# Sheet7.net
KiCad netlist of a schematic drawn in Altium Designer
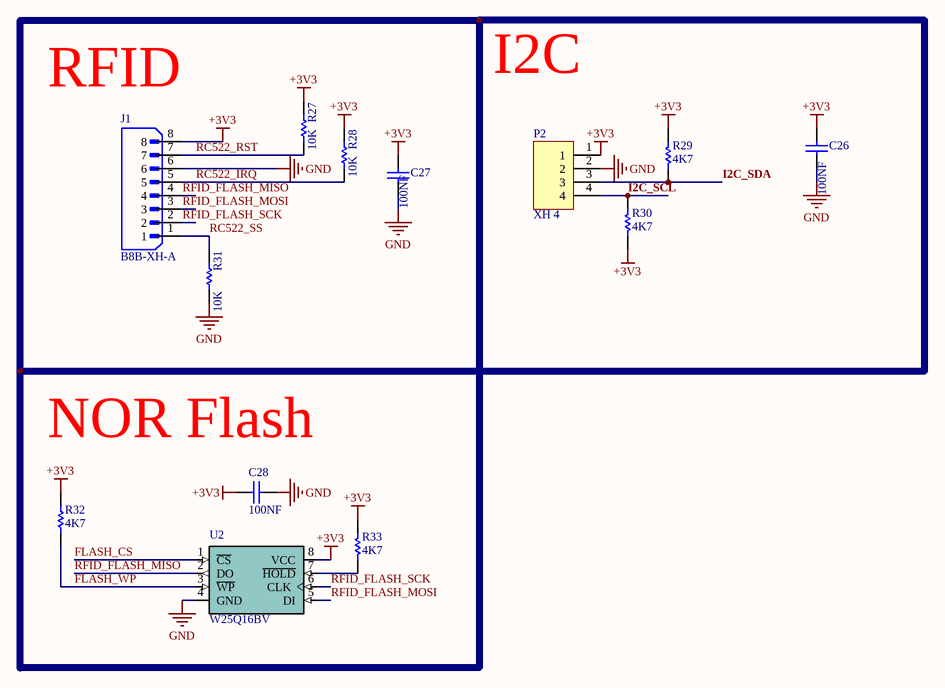
[diagram p0: Sheet7.SchDoc]

(export (version "E")
  (design (tool "Eeschema 10.0.6"))
  (components
    (comp (ref "C26")
      (value "100NF")
      (footprint "CAP0603")
      (description "TOTAL CAPACITOR SMD PACK")
      (fields (field (name "DESIGNER") "Abbas Basereh"))
      (libsource (lib "Altium") (part "CAP SMD PACKAGE"))
    )
    (comp (ref "C27")
      (value "100NF")
      (footprint "CAP0603")
      (description "TOTAL CAPACITOR SMD PACK")
      (fields (field (name "DESIGNER") "Abbas Basereh"))
      (libsource (lib "Altium") (part "CAP SMD PACKAGE"))
    )
    (comp (ref "C28")
      (value "100NF")
      (footprint "CAP0603")
      (description "TOTAL CAPACITOR SMD PACK")
      (fields (field (name "DESIGNER") "Abbas Basereh"))
      (libsource (lib "Altium") (part "CAP SMD PACKAGE"))
    )
    (comp (ref "J1")
      (value "B8B-XH-A")
      (footprint "JST_B8B-XH-A")
      (description "Connector Header Through Hole 8 position 0.098 (2.50mm)")
      (fields (field (name "MF") "JST"))
      (libsource (lib "altium-import") (part "root_2_B8B-XH-A_"))
    )
    (comp (ref "P2")
      (value "XH 4")
      (footprint "XH 4 PIN")
      (description "Conector XH 4 Pin")
      (libsource (lib "XH Connector") (part "Conector XH 4 Pin"))
    )
    (comp (ref "R27")
      (value "10K")
      (footprint "R0603")
      (description "Resistor SMD 0603")
      (libsource (lib "Resistor") (part "Resistor SMD 0603"))
    )
    (comp (ref "R28")
      (value "10K")
      (footprint "R0603")
      (description "Resistor SMD 0603")
      (libsource (lib "Resistor") (part "Resistor SMD 0603"))
    )
    (comp (ref "R29")
      (value "4K7")
      (footprint "R0603")
      (description "Resistor SMD 0603")
      (libsource (lib "Resistor") (part "Resistor SMD 0603"))
    )
    (comp (ref "R30")
      (value "4K7")
      (footprint "R0603")
      (description "Resistor SMD 0603")
      (libsource (lib "Resistor") (part "Resistor SMD 0603"))
    )
    (comp (ref "R31")
      (value "10K")
      (footprint "R0603")
      (description "Resistor SMD 0603")
      (libsource (lib "Resistor") (part "Resistor SMD 0603"))
    )
    (comp (ref "R32")
      (value "4K7")
      (footprint "R0603")
      (description "Resistor SMD 0603")
      (libsource (lib "Resistor") (part "Resistor SMD 0603"))
    )
    (comp (ref "R33")
      (value "4K7")
      (footprint "R0603")
      (description "Resistor SMD 0603")
      (libsource (lib "Resistor") (part "Resistor SMD 0603"))
    )
    (comp (ref "U2")
      (value "W25Q16BV")
      (footprint "SO08")
      (description "Flash, pin, soic, flash, Memory, Semiconductors and Actives, serial, ic")
      (libsource (lib "Practical") (part "W25Q16BV"))
    )
  )
  (nets
    (net (code "1") (name "+3V3") (class "Default")
      (node (ref "C26") (pin "2") (pinfunction "2_2") (pintype "passive"))
      (node (ref "C27") (pin "2") (pinfunction "2_2") (pintype "passive"))
      (node (ref "C28") (pin "2") (pinfunction "2_2") (pintype "passive"))
      (node (ref "J1") (pin "8") (pinfunction "8_8") (pintype "passive"))
      (node (ref "P2") (pin "1") (pinfunction "1_1") (pintype "passive"))
      (node (ref "R27") (pin "2") (pinfunction "2_2") (pintype "passive"))
      (node (ref "R28") (pin "2") (pinfunction "2_2") (pintype "passive"))
      (node (ref "R29") (pin "1") (pinfunction "1_1") (pintype "passive"))
      (node (ref "R30") (pin "2") (pinfunction "2_2") (pintype "passive"))
      (node (ref "R32") (pin "1") (pinfunction "1_1") (pintype "passive"))
      (node (ref "R33") (pin "1") (pinfunction "1_1") (pintype "passive"))
      (node (ref "U2") (pin "8") (pinfunction "VCC_8") (pintype "power_in"))
    )
    (net (code "2") (name "/FLASH_CS") (class "Default")
      (node (ref "U2") (pin "1") (pinfunction "~{CS}_1") (pintype "input"))
    )
    (net (code "3") (name "/FLASH_WP") (class "Default")
      (node (ref "R32") (pin "2") (pinfunction "2_2") (pintype "passive"))
      (node (ref "U2") (pin "3") (pinfunction "~{WP}_3") (pintype "input"))
    )
    (net (code "4") (name "/I2C_SCL") (class "Default")
      (node (ref "P2") (pin "4") (pinfunction "4_4") (pintype "passive"))
      (node (ref "R30") (pin "1") (pinfunction "1_1") (pintype "passive"))
    )
    (net (code "5") (name "/I2C_SDA") (class "Default")
      (node (ref "P2") (pin "3") (pinfunction "3_3") (pintype "passive"))
      (node (ref "R29") (pin "2") (pinfunction "2_2") (pintype "passive"))
    )
    (net (code "6") (name "/RC522_IRQ") (class "Default")
      (node (ref "J1") (pin "5") (pinfunction "5_5") (pintype "passive"))
      (node (ref "R28") (pin "1") (pinfunction "1_1") (pintype "passive"))
    )
    (net (code "7") (name "/RC522_RST") (class "Default")
      (node (ref "J1") (pin "7") (pinfunction "7_7") (pintype "passive"))
      (node (ref "R27") (pin "1") (pinfunction "1_1") (pintype "passive"))
    )
    (net (code "8") (name "/RC522_SS") (class "Default")
      (node (ref "J1") (pin "1") (pinfunction "1_1") (pintype "passive"))
      (node (ref "R31") (pin "2") (pinfunction "2_2") (pintype "passive"))
    )
    (net (code "9") (name "/RFID_FLASH_MISO") (class "Default")
      (node (ref "J1") (pin "4") (pinfunction "4_4") (pintype "passive"))
      (node (ref "U2") (pin "2") (pinfunction "DO_2") (pintype "output"))
    )
    (net (code "10") (name "/RFID_FLASH_MOSI") (class "Default")
      (node (ref "J1") (pin "3") (pinfunction "3_3") (pintype "passive"))
      (node (ref "U2") (pin "5") (pinfunction "DI_5") (pintype "input"))
    )
    (net (code "11") (name "/RFID_FLASH_SCK") (class "Default")
      (node (ref "J1") (pin "2") (pinfunction "2_2") (pintype "passive"))
      (node (ref "U2") (pin "6") (pinfunction "CLK_6") (pintype "input"))
    )
    (net (code "12") (name "GND") (class "Default")
      (node (ref "C26") (pin "1") (pinfunction "1_1") (pintype "passive"))
      (node (ref "C27") (pin "1") (pinfunction "1_1") (pintype "passive"))
      (node (ref "C28") (pin "1") (pinfunction "1_1") (pintype "passive"))
      (node (ref "J1") (pin "6") (pinfunction "6_6") (pintype "passive"))
      (node (ref "P2") (pin "2") (pinfunction "2_2") (pintype "passive"))
      (node (ref "R31") (pin "1") (pinfunction "1_1") (pintype "passive"))
      (node (ref "U2") (pin "4") (pinfunction "GND_4") (pintype "power_in"))
    )
    (net (code "13") (name "Net-(U2-~{HOLD})") (class "Default")
      (node (ref "R33") (pin "2") (pinfunction "2_2") (pintype "passive"))
      (node (ref "U2") (pin "7") (pinfunction "~{HOLD}_7") (pintype "input"))
    )
  )
)
